# 3_-ROTARY_ENCODER.net
KiCad netlist of a schematic drawn in Altium Designer
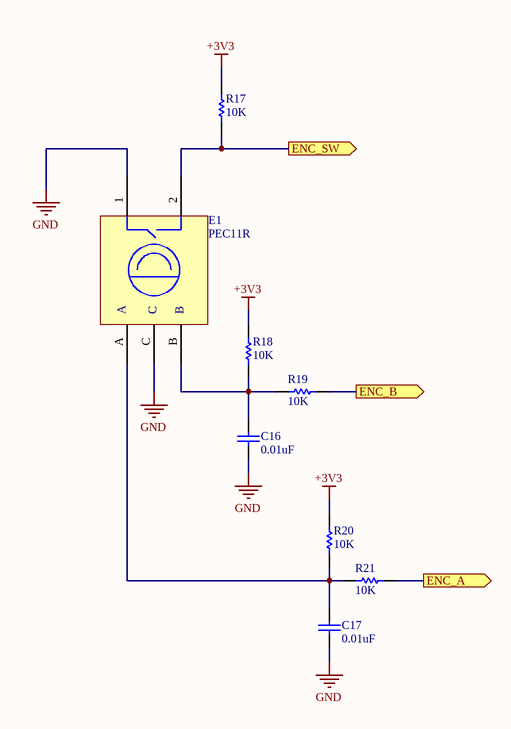
[diagram p0: [3]-ROTARY_ENCODER.SchDoc]

(export (version "E")
  (design (tool "Eeschema 10.0.6"))
  (components
    (comp (ref "C16")
      (value "0.01uF")
      (footprint "CAPC1608N")
      (description "CAP CER 10000PF 50V X7R 0603")
      (fields (field (name "TOLERANCE") "10%") (field (name "VOLTAGE") "50V"))
      (libsource (lib "bitsnio") (part "06035C-103KAT2A"))
    )
    (comp (ref "C17")
      (value "0.01uF")
      (footprint "CAPC1608N")
      (description "CAP CER 10000PF 50V X7R 0603")
      (fields (field (name "TOLERANCE") "10%") (field (name "VOLTAGE") "50V"))
      (libsource (lib "bitsnio") (part "06035C-103KAT2A"))
    )
    (comp (ref "E1")
      (value "PEC11R")
      (footprint "PEC11R")
      (description "ENCODER ROTARY 15MM SHAFT")
      (libsource (lib "bitsnio") (part "PEC11R-4215F-S0024"))
    )
    (comp (ref "R17")
      (value "10K")
      (footprint "RESC1608N")
      (description "RES SMD 10K OHM 5% 1/10W 0603")
      (fields (field (name "TOLERANCE") "5%"))
      (libsource (lib "bitsnio") (part "AC0603JR-0710KL"))
    )
    (comp (ref "R18")
      (value "10K")
      (footprint "RESC1608N")
      (description "RES SMD 10K OHM 5% 1/10W 0603")
      (fields (field (name "TOLERANCE") "5%"))
      (libsource (lib "bitsnio") (part "AC0603JR-0710KL"))
    )
    (comp (ref "R19")
      (value "10K")
      (footprint "RESC1608N")
      (description "RES SMD 10K OHM 5% 1/10W 0603")
      (fields (field (name "TOLERANCE") "5%"))
      (libsource (lib "bitsnio") (part "AC0603JR-0710KL"))
    )
    (comp (ref "R20")
      (value "10K")
      (footprint "RESC1608N")
      (description "RES SMD 10K OHM 5% 1/10W 0603")
      (fields (field (name "TOLERANCE") "5%"))
      (libsource (lib "bitsnio") (part "AC0603JR-0710KL"))
    )
    (comp (ref "R21")
      (value "10K")
      (footprint "RESC1608N")
      (description "RES SMD 10K OHM 5% 1/10W 0603")
      (fields (field (name "TOLERANCE") "5%"))
      (libsource (lib "bitsnio") (part "AC0603JR-0710KL"))
    )
  )
  (nets
    (net (code "1") (name "+3V3") (class "Default")
      (node (ref "R17") (pin "2") (pinfunction "2_2") (pintype "passive"))
      (node (ref "R18") (pin "2") (pinfunction "2_2") (pintype "passive"))
      (node (ref "R20") (pin "2") (pinfunction "2_2") (pintype "passive"))
    )
    (net (code "2") (name "/ENC_A") (class "Default")
      (node (ref "R21") (pin "1") (pinfunction "1_1") (pintype "passive"))
    )
    (net (code "3") (name "/ENC_B") (class "Default")
      (node (ref "R19") (pin "1") (pinfunction "1_1") (pintype "passive"))
    )
    (net (code "4") (name "/ENC_SW") (class "Default")
      (node (ref "E1") (pin "2") (pinfunction "2_2") (pintype "passive"))
      (node (ref "R17") (pin "1") (pinfunction "1_1") (pintype "passive"))
    )
    (net (code "5") (name "GND") (class "Default")
      (node (ref "C16") (pin "1") (pinfunction "1_1") (pintype "passive"))
      (node (ref "C17") (pin "1") (pinfunction "1_1") (pintype "passive"))
      (node (ref "E1") (pin "1") (pinfunction "1_1") (pintype "passive"))
      (node (ref "E1") (pin "C") (pinfunction "C_C") (pintype "passive"))
    )
    (net (code "6") (name "Net-(C16-Pad2)") (class "Default")
      (node (ref "C16") (pin "2") (pinfunction "2_2") (pintype "passive"))
      (node (ref "E1") (pin "B") (pinfunction "B_B") (pintype "passive"))
      (node (ref "R18") (pin "1") (pinfunction "1_1") (pintype "passive"))
      (node (ref "R19") (pin "2") (pinfunction "2_2") (pintype "passive"))
    )
    (net (code "7") (name "Net-(C17-Pad2)") (class "Default")
      (node (ref "C17") (pin "2") (pinfunction "2_2") (pintype "passive"))
      (node (ref "E1") (pin "A") (pinfunction "A_A") (pintype "passive"))
      (node (ref "R20") (pin "1") (pinfunction "1_1") (pintype "passive"))
      (node (ref "R21") (pin "2") (pinfunction "2_2") (pintype "passive"))
    )
  )
)
